# MD015A_MCU_USB2HUB.net
KiCad netlist of a schematic drawn in Altium Designer
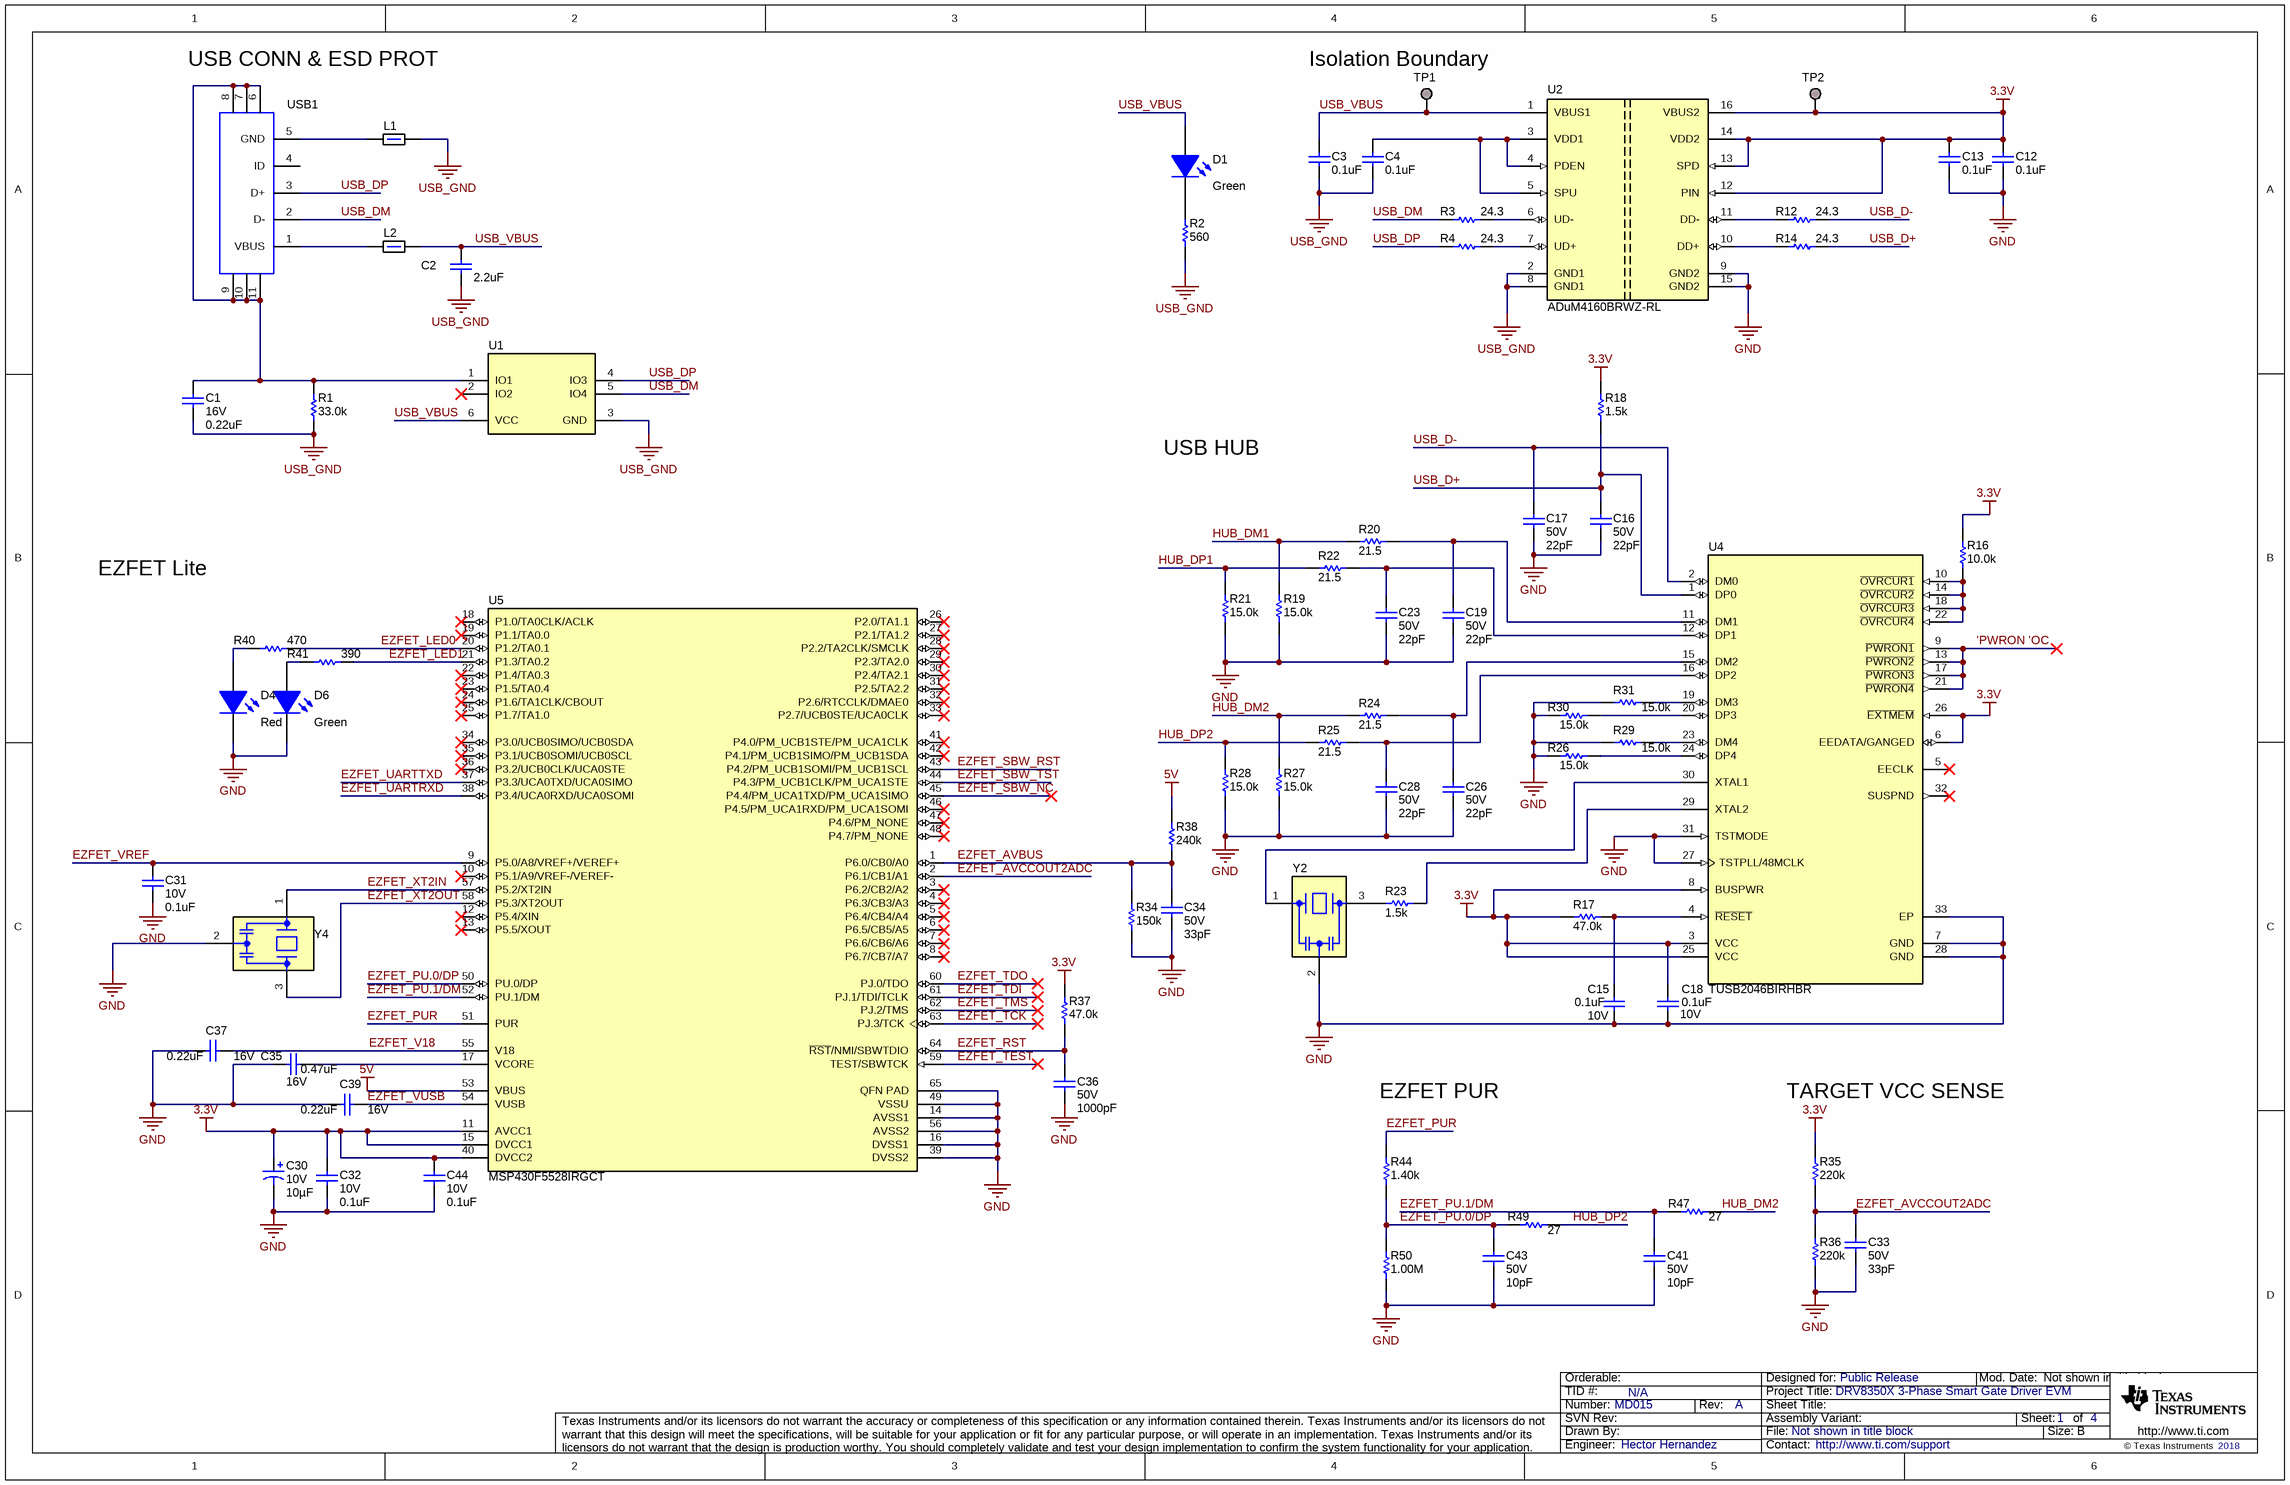
[diagram p0: MD015A_MCU_USB2HUB.SchDoc]

(export (version "E")
  (design (tool "Eeschema 10.0.6"))
  (components
    (comp (ref "C1")
      (value "GRM155R71C224KA12D")
      (footprint "0402L")
      (description "CAP, CERM, 0.22 uF, 16 V, +/- 10%, X7R, 0402")
      (fields
        (field (name "MANUFACTURER") "MuRata")
        (field (name "VDC_V") "16V")
        (field (name "VALUEDISPLAYED") "0.22uF")
      )
      (libsource (lib "Altium Vault - TI") (part "Capacitor"))
    )
    (comp (ref "C2")
      (value "GRM155R60J225KE95D")
      (footprint "0402L")
      (description "CAP, CERM, 2.2 uF, 6.3 V, +/- 10%, X5R, 0402")
      (fields (field (name "VALUEDISPLAYED") "2.2uF") (field (name "MANUFACTURER") "MuRata"))
      (libsource (lib "Altium Vault - TI") (part "Capacitor"))
    )
    (comp (ref "C3")
      (value "GRM155R71A104KA01D")
      (footprint "0402L")
      (description "CAP, CERM, 0.1 uF, 10 V, +/- 10%, X7R, 0402")
      (fields (field (name "VALUEDISPLAYED") "0.1uF") (field (name "MANUFACTURER") "MuRata"))
      (libsource (lib "Altium Vault - TI") (part "Capacitor"))
    )
    (comp (ref "C4")
      (value "GRM155R71A104KA01D")
      (footprint "0402L")
      (description "CAP, CERM, 0.1 uF, 10 V, +/- 10%, X7R, 0402")
      (fields (field (name "VALUEDISPLAYED") "0.1uF") (field (name "MANUFACTURER") "MuRata"))
      (libsource (lib "Altium Vault - TI") (part "Capacitor"))
    )
    (comp (ref "C12")
      (value "GRM155R71A104KA01D")
      (footprint "0402L")
      (description "CAP, CERM, 0.1 uF, 10 V, +/- 10%, X7R, 0402")
      (fields (field (name "VALUEDISPLAYED") "0.1uF") (field (name "MANUFACTURER") "MuRata"))
      (libsource (lib "Altium Vault - TI") (part "Capacitor"))
    )
    (comp (ref "C13")
      (value "GRM155R71A104KA01D")
      (footprint "0402L")
      (description "CAP, CERM, 0.1 uF, 10 V, +/- 10%, X7R, 0402")
      (fields (field (name "VALUEDISPLAYED") "0.1uF") (field (name "MANUFACTURER") "MuRata"))
      (libsource (lib "Altium Vault - TI") (part "Capacitor"))
    )
    (comp (ref "C15")
      (value "885012105010")
      (footprint "0402L")
      (description "CAP, CERM, 0.1 uF, 10 V, +/- 20%, X5R, 0402")
      (fields
        (field (name "MANUFACTURER") "Wurth Elektronik")
        (field (name "VDC_V") "10V")
        (field (name "VALUEDISPLAYED") "0.1uF")
      )
      (libsource (lib "Altium Vault - TI") (part "Capacitor"))
    )
    (comp (ref "C16")
      (value "C1005C0G1H220J050BA")
      (footprint "0402L")
      (description "CAP, CERM, 22 pF, 50 V, +/- 5%, C0G/NP0, 0402")
      (fields
        (field (name "MANUFACTURER") "TDK")
        (field (name "VDC_V") "50V")
        (field (name "VALUEDISPLAYED") "22pF")
      )
      (libsource (lib "Altium Vault - TI") (part "Capacitor"))
    )
    (comp (ref "C17")
      (value "C1005C0G1H220J050BA")
      (footprint "0402L")
      (description "CAP, CERM, 22 pF, 50 V, +/- 5%, C0G/NP0, 0402")
      (fields
        (field (name "MANUFACTURER") "TDK")
        (field (name "VDC_V") "50V")
        (field (name "VALUEDISPLAYED") "22pF")
      )
      (libsource (lib "Altium Vault - TI") (part "Capacitor"))
    )
    (comp (ref "C18")
      (value "885012105010")
      (footprint "0402L")
      (description "CAP, CERM, 0.1 uF, 10 V, +/- 20%, X5R, 0402")
      (fields
        (field (name "MANUFACTURER") "Wurth Elektronik")
        (field (name "VDC_V") "10V")
        (field (name "VALUEDISPLAYED") "0.1uF")
      )
      (libsource (lib "Altium Vault - TI") (part "Capacitor"))
    )
    (comp (ref "C19")
      (value "C1005C0G1H220J050BA")
      (footprint "0402L")
      (description "CAP, CERM, 22 pF, 50 V, +/- 5%, C0G/NP0, 0402")
      (fields
        (field (name "MANUFACTURER") "TDK")
        (field (name "VDC_V") "50V")
        (field (name "VALUEDISPLAYED") "22pF")
      )
      (libsource (lib "Altium Vault - TI") (part "Capacitor"))
    )
    (comp (ref "C23")
      (value "C1005C0G1H220J050BA")
      (footprint "0402L")
      (description "CAP, CERM, 22 pF, 50 V, +/- 5%, C0G/NP0, 0402")
      (fields
        (field (name "MANUFACTURER") "TDK")
        (field (name "VDC_V") "50V")
        (field (name "VALUEDISPLAYED") "22pF")
      )
      (libsource (lib "Altium Vault - TI") (part "Capacitor"))
    )
    (comp (ref "C26")
      (value "C1005C0G1H220J050BA")
      (footprint "0402L")
      (description "CAP, CERM, 22 pF, 50 V, +/- 5%, C0G/NP0, 0402")
      (fields
        (field (name "MANUFACTURER") "TDK")
        (field (name "VDC_V") "50V")
        (field (name "VALUEDISPLAYED") "22pF")
      )
      (libsource (lib "Altium Vault - TI") (part "Capacitor"))
    )
    (comp (ref "C28")
      (value "C1005C0G1H220J050BA")
      (footprint "0402L")
      (description "CAP, CERM, 22 pF, 50 V, +/- 5%, C0G/NP0, 0402")
      (fields
        (field (name "MANUFACTURER") "TDK")
        (field (name "VDC_V") "50V")
        (field (name "VALUEDISPLAYED") "22pF")
      )
      (libsource (lib "Altium Vault - TI") (part "Capacitor"))
    )
    (comp (ref "C30")
      (value "T520A106M010ATE080")
      (footprint "3216-18")
      (description "CAP, Tantalum Polymer, 10 µF, 10 V,+/- 20%, 0.08 ohm, 3216-18 SMD")
      (fields
        (field (name "VDC_V") "10V")
        (field (name "MANUFACTURER") "Kemet")
        (field (name "VALUEDISPLAYED") "10µF")
      )
      (libsource (lib "Altium Vault - TI") (part "Cap_Polarized"))
    )
    (comp (ref "C31")
      (value "885012105010")
      (footprint "0402L")
      (description "CAP, CERM, 0.1 uF, 10 V, +/- 20%, X5R, 0402")
      (fields
        (field (name "MANUFACTURER") "Wurth Elektronik")
        (field (name "VDC_V") "10V")
        (field (name "VALUEDISPLAYED") "0.1uF")
      )
      (libsource (lib "Altium Vault - TI") (part "Capacitor"))
    )
    (comp (ref "C32")
      (value "885012105010")
      (footprint "0402L")
      (description "CAP, CERM, 0.1 uF, 10 V, +/- 20%, X5R, 0402")
      (fields
        (field (name "MANUFACTURER") "Wurth Elektronik")
        (field (name "VDC_V") "10V")
        (field (name "VALUEDISPLAYED") "0.1uF")
      )
      (libsource (lib "Altium Vault - TI") (part "Capacitor"))
    )
    (comp (ref "C33")
      (value "C0603C330J5GACTU")
      (footprint "0603L")
      (description "CAP, CERM, 33 pF, 50 V, +/- 5%, C0G/NP0, 0603")
      (fields
        (field (name "MANUFACTURER") "Kemet")
        (field (name "VDC_V") "50V")
        (field (name "VALUEDISPLAYED") "33pF")
      )
      (libsource (lib "Altium Vault - TI") (part "Capacitor"))
    )
    (comp (ref "C34")
      (value "C0603C330J5GACTU")
      (footprint "0603L")
      (description "CAP, CERM, 33 pF, 50 V, +/- 5%, C0G/NP0, 0603")
      (fields
        (field (name "MANUFACTURER") "Kemet")
        (field (name "VDC_V") "50V")
        (field (name "VALUEDISPLAYED") "33pF")
      )
      (libsource (lib "Altium Vault - TI") (part "Capacitor"))
    )
    (comp (ref "C35")
      (value "GCM188R71C474KA55D")
      (footprint "0603L")
      (description "CAP, CERM, 0.47 uF, 16 V, +/- 10%, X7R, AEC-Q200 Grade 1, 0603")
      (fields
        (field (name "MANUFACTURER") "MuRata")
        (field (name "VDC_V") "16V")
        (field (name "VALUEDISPLAYED") "0.47uF")
      )
      (libsource (lib "Altium Vault - TI") (part "Capacitor"))
    )
    (comp (ref "C36")
      (value "885012205061")
      (footprint "0402L")
      (description "CAP, CERM, 1000 pF, 50 V, +/- 10%, X7R, 0402")
      (fields
        (field (name "MANUFACTURER") "Wurth Elektronik")
        (field (name "VDC_V") "50V")
        (field (name "VALUEDISPLAYED") "1000pF")
      )
      (libsource (lib "Altium Vault - TI") (part "Capacitor"))
    )
    (comp (ref "C37")
      (value "C1005X5R1C224K050BB")
      (footprint "0402L")
      (description "CAP, CERM, 0.22 uF, 16 V, +/- 10%, X5R, 0402")
      (fields
        (field (name "MANUFACTURER") "TDK")
        (field (name "VDC_V") "16V")
        (field (name "VALUEDISPLAYED") "0.22uF")
      )
      (libsource (lib "Altium Vault - TI") (part "Capacitor"))
    )
    (comp (ref "C39")
      (value "C1005X5R1C224K050BB")
      (footprint "0402L")
      (description "CAP, CERM, 0.22 uF, 16 V, +/- 10%, X5R, 0402")
      (fields
        (field (name "MANUFACTURER") "TDK")
        (field (name "VDC_V") "16V")
        (field (name "VALUEDISPLAYED") "0.22uF")
      )
      (libsource (lib "Altium Vault - TI") (part "Capacitor"))
    )
    (comp (ref "C41")
      (value "04025U100CAT2A")
      (footprint "0402L")
      (description "CAP, CERM, 10 pF, 50 V,+/- 2.5%, C0G/NP0, AEC-Q200 Grade 1, 0402")
      (fields
        (field (name "MANUFACTURER") "AVX")
        (field (name "VDC_V") "50V")
        (field (name "VALUEDISPLAYED") "10pF")
      )
      (libsource (lib "Altium Vault - TI") (part "Capacitor"))
    )
    (comp (ref "C43")
      (value "04025U100CAT2A")
      (footprint "0402L")
      (description "CAP, CERM, 10 pF, 50 V,+/- 2.5%, C0G/NP0, AEC-Q200 Grade 1, 0402")
      (fields
        (field (name "MANUFACTURER") "AVX")
        (field (name "VDC_V") "50V")
        (field (name "VALUEDISPLAYED") "10pF")
      )
      (libsource (lib "Altium Vault - TI") (part "Capacitor"))
    )
    (comp (ref "C44")
      (value "885012105010")
      (footprint "0402L")
      (description "CAP, CERM, 0.1 uF, 10 V, +/- 20%, X5R, 0402")
      (fields
        (field (name "MANUFACTURER") "Wurth Elektronik")
        (field (name "VDC_V") "10V")
        (field (name "VALUEDISPLAYED") "0.1uF")
      )
      (libsource (lib "Altium Vault - TI") (part "Capacitor"))
    )
    (comp (ref "D1")
      (value "Green")
      (footprint "LTST-C170KGKT_Green")
      (description "LED, Green, SMD")
      (fields (field (name "MANUFACTURER") "Lite-On") (field (name "PARTNUMBER") "LTST-C170KGKT"))
      (libsource (lib "Altium Vault - TI") (part "LED"))
    )
    (comp (ref "D4")
      (value "Red")
      (footprint "LED_LTST-C190_Red")
      (description "LED, Red, SMD")
      (fields (field (name "MANUFACTURER") "Lite-On") (field (name "PARTNUMBER") "LTST-C190CKT"))
      (libsource (lib "Altium Vault - TI") (part "LED"))
    )
    (comp (ref "D6")
      (value "Green")
      (footprint "LED_LTST-C190")
      (description "LED, Green, SMD")
      (fields (field (name "MANUFACTURER") "Lite-On") (field (name "PARTNUMBER") "LTST-C190GKT"))
      (libsource (lib "Altium Vault - TI") (part "LED"))
    )
    (comp (ref "L1")
      (value "742792620")
      (footprint "0603L")
      (description "Ferrite Bead, 100 ohm @ 100 MHz, 0.5 A, 0603")
      (fields (field (name "MANUFACTURER") "Wurth Elektronik"))
      (libsource (lib "Altium Vault - TI") (part "Ferrite_Bead"))
    )
    (comp (ref "L2")
      (value "742792620")
      (footprint "0603L")
      (description "Ferrite Bead, 100 ohm @ 100 MHz, 0.5 A, 0603")
      (fields (field (name "MANUFACTURER") "Wurth Elektronik"))
      (libsource (lib "Altium Vault - TI") (part "Ferrite_Bead"))
    )
    (comp (ref "R1")
      (value "RC0402FR-0733KL")
      (footprint "0402L")
      (description "RES, 33.0 k, 1%, 0.063 W, 0402")
      (fields (field (name "MANUFACTURER") "Yageo America") (field (name "VALUEDISPLAYED") "33.0k"))
      (libsource (lib "Altium Vault - TI") (part "Resistor"))
    )
    (comp (ref "R2")
      (value "RG1608P-561-B-T5")
      (footprint "0603L")
      (description "RES, 560, 0.1%, 0.1 W, 0603")
      (fields (field (name "MANUFACTURER") "Susumu Co Ltd") (field (name "VALUEDISPLAYED") "560"))
      (libsource (lib "Altium Vault - TI") (part "Resistor"))
    )
    (comp (ref "R3")
      (value "CRCW040224R3FKED")
      (footprint "0402L")
      (description "RES, 24.3, 1%, 0.063 W, AEC-Q200 Grade 0, 0402")
      (fields (field (name "VALUEDISPLAYED") "24.3") (field (name "MANUFACTURER") "Vishay-Dale"))
      (libsource (lib "Altium Vault - TI") (part "Resistor"))
    )
    (comp (ref "R4")
      (value "CRCW040224R3FKED")
      (footprint "0402L")
      (description "RES, 24.3, 1%, 0.063 W, AEC-Q200 Grade 0, 0402")
      (fields (field (name "VALUEDISPLAYED") "24.3") (field (name "MANUFACTURER") "Vishay-Dale"))
      (libsource (lib "Altium Vault - TI") (part "Resistor"))
    )
    (comp (ref "R12")
      (value "CRCW040224R3FKED")
      (footprint "0402L")
      (description "RES, 24.3, 1%, 0.063 W, AEC-Q200 Grade 0, 0402")
      (fields (field (name "VALUEDISPLAYED") "24.3") (field (name "MANUFACTURER") "Vishay-Dale"))
      (libsource (lib "Altium Vault - TI") (part "Resistor"))
    )
    (comp (ref "R14")
      (value "CRCW040224R3FKED")
      (footprint "0402L")
      (description "RES, 24.3, 1%, 0.063 W, AEC-Q200 Grade 0, 0402")
      (fields (field (name "VALUEDISPLAYED") "24.3") (field (name "MANUFACTURER") "Vishay-Dale"))
      (libsource (lib "Altium Vault - TI") (part "Resistor"))
    )
    (comp (ref "R16")
      (value "MCR01MRTF1002")
      (footprint "0402L")
      (description "RES, 10.0 k, 0.1%, 0.063 W, 0402")
      (fields (field (name "MANUFACTURER") "Rohm") (field (name "VALUEDISPLAYED") "10.0k"))
      (libsource (lib "Altium Vault - TI") (part "Resistor"))
    )
    (comp (ref "R17")
      (value "RC0402FR-0747KL")
      (footprint "0402L")
      (description "RES, 47.0 k, 1%, 0.0625 W, 0402")
      (fields (field (name "MANUFACTURER") "Yageo America") (field (name "VALUEDISPLAYED") "47.0k"))
      (libsource (lib "Altium Vault - TI") (part "Resistor"))
    )
    (comp (ref "R18")
      (value "CRCW04021K50JNED")
      (footprint "0402L")
      (description "RES, 1.5 k, 5%, 0.063 W, AEC-Q200 Grade 0, 0402")
      (fields (field (name "MANUFACTURER") "Vishay-Dale") (field (name "VALUEDISPLAYED") "1.5k"))
      (libsource (lib "Altium Vault - TI") (part "Resistor"))
    )
    (comp (ref "R19")
      (value "RC0402FR-0715KL")
      (footprint "0402L")
      (description "RES, 15.0 k, 1%, 0.063 W, 0402")
      (fields (field (name "MANUFACTURER") "Yageo America") (field (name "VALUEDISPLAYED") "15.0k"))
      (libsource (lib "Altium Vault - TI") (part "Resistor"))
    )
    (comp (ref "R20")
      (value "CRCW040221R5FKED")
      (footprint "0402L")
      (description "RES, 21.5, 1%, 0.063 W, AEC-Q200 Grade 0, 0402")
      (fields (field (name "MANUFACTURER") "Vishay-Dale") (field (name "VALUEDISPLAYED") "21.5"))
      (libsource (lib "Altium Vault - TI") (part "Resistor"))
    )
    (comp (ref "R21")
      (value "RC0402FR-0715KL")
      (footprint "0402L")
      (description "RES, 15.0 k, 1%, 0.063 W, 0402")
      (fields (field (name "MANUFACTURER") "Yageo America") (field (name "VALUEDISPLAYED") "15.0k"))
      (libsource (lib "Altium Vault - TI") (part "Resistor"))
    )
    (comp (ref "R22")
      (value "CRCW040221R5FKED")
      (footprint "0402L")
      (description "RES, 21.5, 1%, 0.063 W, AEC-Q200 Grade 0, 0402")
      (fields (field (name "MANUFACTURER") "Vishay-Dale") (field (name "VALUEDISPLAYED") "21.5"))
      (libsource (lib "Altium Vault - TI") (part "Resistor"))
    )
    (comp (ref "R23")
      (value "CRCW04021K50JNED")
      (footprint "0402L")
      (description "RES, 1.5 k, 5%, 0.063 W, AEC-Q200 Grade 0, 0402")
      (fields (field (name "MANUFACTURER") "Vishay-Dale") (field (name "VALUEDISPLAYED") "1.5k"))
      (libsource (lib "Altium Vault - TI") (part "Resistor"))
    )
    (comp (ref "R24")
      (value "CRCW040221R5FKED")
      (footprint "0402L")
      (description "RES, 21.5, 1%, 0.063 W, AEC-Q200 Grade 0, 0402")
      (fields (field (name "MANUFACTURER") "Vishay-Dale") (field (name "VALUEDISPLAYED") "21.5"))
      (libsource (lib "Altium Vault - TI") (part "Resistor"))
    )
    (comp (ref "R25")
      (value "CRCW040221R5FKED")
      (footprint "0402L")
      (description "RES, 21.5, 1%, 0.063 W, AEC-Q200 Grade 0, 0402")
      (fields (field (name "MANUFACTURER") "Vishay-Dale") (field (name "VALUEDISPLAYED") "21.5"))
      (libsource (lib "Altium Vault - TI") (part "Resistor"))
    )
    (comp (ref "R26")
      (value "RC0402FR-0715KL")
      (footprint "0402L")
      (description "RES, 15.0 k, 1%, 0.063 W, 0402")
      (fields (field (name "MANUFACTURER") "Yageo America") (field (name "VALUEDISPLAYED") "15.0k"))
      (libsource (lib "Altium Vault - TI") (part "Resistor"))
    )
    (comp (ref "R27")
      (value "RC0402FR-0715KL")
      (footprint "0402L")
      (description "RES, 15.0 k, 1%, 0.063 W, 0402")
      (fields (field (name "MANUFACTURER") "Yageo America") (field (name "VALUEDISPLAYED") "15.0k"))
      (libsource (lib "Altium Vault - TI") (part "Resistor"))
    )
    (comp (ref "R28")
      (value "RC0402FR-0715KL")
      (footprint "0402L")
      (description "RES, 15.0 k, 1%, 0.063 W, 0402")
      (fields (field (name "MANUFACTURER") "Yageo America") (field (name "VALUEDISPLAYED") "15.0k"))
      (libsource (lib "Altium Vault - TI") (part "Resistor"))
    )
    (comp (ref "R29")
      (value "RC0402FR-0715KL")
      (footprint "0402L")
      (description "RES, 15.0 k, 1%, 0.063 W, 0402")
      (fields (field (name "MANUFACTURER") "Yageo America") (field (name "VALUEDISPLAYED") "15.0k"))
      (libsource (lib "Altium Vault - TI") (part "Resistor"))
    )
    (comp (ref "R30")
      (value "RC0402FR-0715KL")
      (footprint "0402L")
      (description "RES, 15.0 k, 1%, 0.063 W, 0402")
      (fields (field (name "MANUFACTURER") "Yageo America") (field (name "VALUEDISPLAYED") "15.0k"))
      (libsource (lib "Altium Vault - TI") (part "Resistor"))
    )
    (comp (ref "R31")
      (value "RC0402FR-0715KL")
      (footprint "0402L")
      (description "RES, 15.0 k, 1%, 0.063 W, 0402")
      (fields (field (name "MANUFACTURER") "Yageo America") (field (name "VALUEDISPLAYED") "15.0k"))
      (libsource (lib "Altium Vault - TI") (part "Resistor"))
    )
    (comp (ref "R34")
      (value "ERJ-2RKF1503X")
      (footprint "0402L")
      (description "RES, 150 k, 1%, 0.1 W, AEC-Q200 Grade 0, 0402")
      (fields (field (name "MANUFACTURER") "Panasonic") (field (name "VALUEDISPLAYED") "150k"))
      (libsource (lib "Altium Vault - TI") (part "Resistor"))
    )
    (comp (ref "R35")
      (value "RC0402FR-07220KL")
      (footprint "0402L")
      (description "RES, 220 k, 1%, 0.0625 W, 0402")
      (fields (field (name "MANUFACTURER") "Yageo America") (field (name "VALUEDISPLAYED") "220k"))
      (libsource (lib "Altium Vault - TI") (part "Resistor"))
    )
    (comp (ref "R36")
      (value "RC0402FR-07220KL")
      (footprint "0402L")
      (description "RES, 220 k, 1%, 0.0625 W, 0402")
      (fields (field (name "MANUFACTURER") "Yageo America") (field (name "VALUEDISPLAYED") "220k"))
      (libsource (lib "Altium Vault - TI") (part "Resistor"))
    )
    (comp (ref "R37")
      (value "RC0402FR-0747KL")
      (footprint "0402L")
      (description "RES, 47.0 k, 1%, 0.0625 W, 0402")
      (fields (field (name "MANUFACTURER") "Yageo America") (field (name "VALUEDISPLAYED") "47.0k"))
      (libsource (lib "Altium Vault - TI") (part "Resistor"))
    )
    (comp (ref "R38")
      (value "ERJ-2RKF2403X")
      (footprint "0402L")
      (description "RES, 240 k, 1%, 0.1 W, AEC-Q200 Grade 0, 0402")
      (fields (field (name "MANUFACTURER") "Panasonic") (field (name "VALUEDISPLAYED") "240k"))
      (libsource (lib "Altium Vault - TI") (part "Resistor"))
    )
    (comp (ref "R40")
      (value "ERJ-2RKF4700X")
      (footprint "0402L")
      (description "RES, 470, 1%, 0.1 W, AEC-Q200 Grade 0, 0402")
      (fields (field (name "MANUFACTURER") "Panasonic") (field (name "VALUEDISPLAYED") "470"))
      (libsource (lib "Altium Vault - TI") (part "Resistor"))
    )
    (comp (ref "R41")
      (value "CRCW0402390RJNED")
      (footprint "0402L")
      (description "RES, 390, 5%, 0.063 W, AEC-Q200 Grade 0, 0402")
      (fields (field (name "MANUFACTURER") "Vishay-Dale") (field (name "VALUEDISPLAYED") "390"))
      (libsource (lib "Altium Vault - TI") (part "Resistor"))
    )
    (comp (ref "R44")
      (value "ERJ-2RKF1401X")
      (footprint "0402L")
      (description "RES, 1.40 k, 1%, 0.1 W, 0402")
      (fields (field (name "MANUFACTURER") "Panasonic") (field (name "VALUEDISPLAYED") "1.40k"))
      (libsource (lib "Altium Vault - TI") (part "Resistor"))
    )
    (comp (ref "R47")
      (value "CRCW040227R0JNED")
      (footprint "0402L")
      (description "RES, 27, 5%, 0.063 W, AEC-Q200 Grade 0, 0402")
      (fields (field (name "MANUFACTURER") "Vishay-Dale") (field (name "VALUEDISPLAYED") "27"))
      (libsource (lib "Altium Vault - TI") (part "Resistor"))
    )
    (comp (ref "R49")
      (value "CRCW040227R0JNED")
      (footprint "0402L")
      (description "RES, 27, 5%, 0.063 W, AEC-Q200 Grade 0, 0402")
      (fields (field (name "MANUFACTURER") "Vishay-Dale") (field (name "VALUEDISPLAYED") "27"))
      (libsource (lib "Altium Vault - TI") (part "Resistor"))
    )
    (comp (ref "R50")
      (value "ERJ-2RKF1004X")
      (footprint "0402L")
      (description "RES, 1.00 M, 1%, 0.1 W, 0402")
      (fields (field (name "MANUFACTURER") "Panasonic") (field (name "VALUEDISPLAYED") "1.00M"))
      (libsource (lib "Altium Vault - TI") (part "Resistor"))
    )
    (comp (ref "TP1")
      (value "TP_SM_1MM")
      (footprint "TP_SM_1MM")
      (description "1mm Test Point, SMT")
      (fields (field (name "MANUFACTURER") "Any"))
      (libsource (lib "Altium Vault - TI") (part "TESTPOINT"))
    )
    (comp (ref "TP2")
      (value "TP_SM_1MM")
      (footprint "TP_SM_1MM")
      (description "1mm Test Point, SMT")
      (fields (field (name "MANUFACTURER") "Any"))
      (libsource (lib "Altium Vault - TI") (part "TESTPOINT"))
    )
    (comp (ref "U1")
      (value "TPD4E004DRYR")
      (footprint "DRY0006A")
      (description "4-Channel ESD Protection Array for High-Speed Data Interfaces, DRY0006A (USON-6)")
      (fields (field (name "MANUFACTURER") "Texas Instruments"))
      (libsource (lib "Altium Vault - TI") (part "TI-TPD4E004-SON_DRY-6"))
    )
    (comp (ref "U2")
      (value "ADuM4160BRWZ-RL")
      (footprint "SOIC-16")
      (description "Full/Low Speed 5 kV USB Digital Isolator, SOIC-16")
      (fields (field (name "MANUFACTURER") "Analog Devices"))
      (libsource (lib "Altium Vault - TI") (part "ADUM4160"))
    )
    (comp (ref "U4")
      (value "TUSB2046BIRHBR")
      (footprint "RHB0032E")
      (description "4-Port Full-Speed USB Hub, 3.3V, -40 to 85 degC, 32-Pin QFN (RHB), Green (RoHS & no Sb/Br)")
      (fields (field (name "PARTNUMBER") "TUSB2046BIRHBR") (field (name "MANUFACTURER") "Texas Instruments"))
      (libsource (lib "Altium Vault - TI") (part "TI-TUSB2046B-QFN_RHB-32"))
    )
    (comp (ref "U5")
      (value "MSP430F5528IRGCT")
      (footprint "RGC0064B")
      (fields
        (field (name "PARTNUMBER") "MSP430F5528IRGCT")
        (field (name "MANUFACTURER") "Texas Instruments")
        (field (name "ALTERNATE PARTNUMBER") "MSP430F5528IRGCR")
      )
      (libsource (lib "Altium Vault - TI") (part "MSP430F5528IRGC"))
    )
    (comp (ref "USB1")
      (value "1051640001")
      (footprint "Molex_1051640001")
      (description "Receptacle, USB 2.0, Micro B, 5 Position, R/A, SMT")
      (fields (field (name "MANUFACTURER") "Molex"))
      (libsource (lib "Altium Vault - TI") (part "CONN_USB_MicroMini_6Shld"))
    )
    (comp (ref "Y2")
      (value "CSTNR6M00GH5L000R0")
      (footprint "MuRata_CSTNR")
      (description "Oscillator, 6 MHz, 700 ppm, 39 pF, SMD")
      (fields (field (name "MANUFACTURER") "MuRata"))
      (libsource (lib "") (part "OSC_CSTCE_1"))
    )
    (comp (ref "Y4")
      (value "CSTNR4M00GH5L000R0")
      (footprint "MuRata_CSTNR")
      (description "Oscillator, 4 MHz, 700 ppm, 39 pF, SMD")
      (fields (field (name "MANUFACTURER") "MuRata"))
      (libsource (lib "Altium Vault - TI") (part "OSC_CSTCE"))
    )
  )
  (nets
    (net (code "1") (name "/'PWRON 'OC") (class "Default")
      (node (ref "U4") (pin "13") (pinfunction "~{PWRON2}_13") (pintype "output"))
      (node (ref "U4") (pin "17") (pinfunction "~{PWRON3}_17") (pintype "output"))
      (node (ref "U4") (pin "21") (pinfunction "~{PWRON4}_21") (pintype "output"))
      (node (ref "U4") (pin "9") (pinfunction "~{PWRON1}_9") (pintype "output"))
    )
    (net (code "2") (name "/EZFET_AVBUS") (class "Default")
      (node (ref "C34") (pin "1") (pinfunction "1_1") (pintype "passive"))
      (node (ref "R34") (pin "2") (pinfunction "2_2") (pintype "passive"))
      (node (ref "R38") (pin "2") (pinfunction "2_2") (pintype "passive"))
      (node (ref "U5") (pin "1") (pinfunction "P6.0/CB0/A0_1") (pintype "bidirectional"))
    )
    (net (code "3") (name "/EZFET_AVCCOUT2ADC") (class "Default")
      (node (ref "C33") (pin "1") (pinfunction "1_1") (pintype "passive"))
      (node (ref "R35") (pin "1") (pinfunction "1_1") (pintype "passive"))
      (node (ref "R36") (pin "2") (pinfunction "2_2") (pintype "passive"))
      (node (ref "U5") (pin "2") (pinfunction "P6.1/CB1/A1_2") (pintype "bidirectional"))
    )
    (net (code "4") (name "/EZFET_LED0") (class "Default")
      (node (ref "R40") (pin "2") (pinfunction "2_2") (pintype "passive"))
      (node (ref "U5") (pin "20") (pinfunction "P1.2/TA0.1_20") (pintype "bidirectional"))
    )
    (net (code "5") (name "/EZFET_LED1") (class "Default")
      (node (ref "R41") (pin "1") (pinfunction "1_1") (pintype "passive"))
      (node (ref "U5") (pin "21") (pinfunction "P1.3/TA0.2_21") (pintype "bidirectional"))
    )
    (net (code "6") (name "/EZFET_PU.0{slash}DP") (class "Default")
      (node (ref "C43") (pin "1") (pinfunction "1_1") (pintype "passive"))
      (node (ref "R44") (pin "1") (pinfunction "1_1") (pintype "passive"))
      (node (ref "R49") (pin "2") (pinfunction "2_2") (pintype "passive"))
      (node (ref "R50") (pin "2") (pinfunction "2_2") (pintype "passive"))
      (node (ref "U5") (pin "50") (pinfunction "PU.0/DP_50") (pintype "bidirectional"))
    )
    (net (code "7") (name "/EZFET_PU.1{slash}DM") (class "Default")
      (node (ref "C41") (pin "1") (pinfunction "1_1") (pintype "passive"))
      (node (ref "R47") (pin "2") (pinfunction "2_2") (pintype "passive"))
      (node (ref "U5") (pin "52") (pinfunction "PU.1/DM_52") (pintype "bidirectional"))
    )
    (net (code "8") (name "/EZFET_PUR") (class "Default")
      (node (ref "R44") (pin "2") (pinfunction "2_2") (pintype "passive"))
      (node (ref "U5") (pin "51") (pinfunction "PUR_51") (pintype "passive"))
    )
    (net (code "9") (name "/EZFET_RST") (class "Default")
      (node (ref "C36") (pin "1") (pinfunction "1_1") (pintype "passive"))
      (node (ref "R37") (pin "1") (pinfunction "1_1") (pintype "passive"))
      (node (ref "U5") (pin "64") (pinfunction "~{RST}/NMI/SBWTDIO_64") (pintype "bidirectional"))
    )
    (net (code "10") (name "/EZFET_SBW_NC") (class "Default")
      (node (ref "U5") (pin "45") (pinfunction "P4.4/PM_UCA1TXD/PM_UCA1SIMO_45") (pintype "bidirectional+no_connect"))
    )
    (net (code "11") (name "/EZFET_SBW_RST") (class "Default")
      (node (ref "U5") (pin "43") (pinfunction "P4.2/PM_UCB1SOMI/PM_UCB1SCL_43") (pintype "bidirectional"))
    )
    (net (code "12") (name "/EZFET_SBW_TST") (class "Default")
      (node (ref "U5") (pin "44") (pinfunction "P4.3/PM_UCB1CLK/PM_UCA1STE_44") (pintype "bidirectional"))
    )
    (net (code "13") (name "/EZFET_TCK") (class "Default")
      (node (ref "U5") (pin "63") (pinfunction "PJ.3/TCK_63") (pintype "bidirectional+no_connect"))
    )
    (net (code "14") (name "/EZFET_TDI") (class "Default")
      (node (ref "U5") (pin "61") (pinfunction "PJ.1/TDI/TCLK_61") (pintype "bidirectional+no_connect"))
    )
    (net (code "15") (name "/EZFET_TDO") (class "Default")
      (node (ref "U5") (pin "60") (pinfunction "PJ.0/TDO_60") (pintype "bidirectional+no_connect"))
    )
    (net (code "16") (name "/EZFET_TEST") (class "Default")
      (node (ref "U5") (pin "59") (pinfunction "TEST/SBWTCK_59") (pintype "input+no_connect"))
    )
    (net (code "17") (name "/EZFET_TMS") (class "Default")
      (node (ref "U5") (pin "62") (pinfunction "PJ.2/TMS_62") (pintype "bidirectional+no_connect"))
    )
    (net (code "18") (name "/EZFET_UARTRXD") (class "Default")
      (node (ref "U5") (pin "38") (pinfunction "P3.4/UCA0RXD/UCA0SOMI_38") (pintype "bidirectional"))
    )
    (net (code "19") (name "/EZFET_UARTTXD") (class "Default")
      (node (ref "U5") (pin "37") (pinfunction "P3.3/UCA0TXD/UCA0SIMO_37") (pintype "bidirectional"))
    )
    (net (code "20") (name "/EZFET_V18") (class "Default")
      (node (ref "C37") (pin "2") (pinfunction "2_2") (pintype "passive"))
      (node (ref "U5") (pin "55") (pinfunction "V18_55") (pintype "passive"))
    )
    (net (code "21") (name "/EZFET_VREF") (class "Default")
      (node (ref "C31") (pin "1") (pinfunction "1_1") (pintype "passive"))
      (node (ref "U5") (pin "9") (pinfunction "P5.0/A8/VREF+/VEREF+_9") (pintype "bidirectional"))
    )
    (net (code "22") (name "/EZFET_VUSB") (class "Default")
      (node (ref "C39") (pin "2") (pinfunction "2_2") (pintype "passive"))
      (node (ref "U5") (pin "54") (pinfunction "VUSB_54") (pintype "power_in"))
    )
    (net (code "23") (name "/EZFET_XT2IN") (class "Default")
      (node (ref "U5") (pin "57") (pinfunction "P5.2/XT2IN_57") (pintype "bidirectional"))
      (node (ref "Y4") (pin "1") (pinfunction "In_1") (pintype "passive"))
    )
    (net (code "24") (name "/EZFET_XT2OUT") (class "Default")
      (node (ref "U5") (pin "58") (pinfunction "P5.3/XT2OUT_58") (pintype "bidirectional"))
      (node (ref "Y4") (pin "3") (pinfunction "Out_3") (pintype "passive"))
    )
    (net (code "25") (name "/HUB_DM1") (class "Default")
      (node (ref "R19") (pin "2") (pinfunction "2_2") (pintype "passive"))
      (node (ref "R20") (pin "2") (pinfunction "2_2") (pintype "passive"))
    )
    (net (code "26") (name "/HUB_DM2") (class "Default")
      (node (ref "R24") (pin "2") (pinfunction "2_2") (pintype "passive"))
      (node (ref "R27") (pin "2") (pinfunction "2_2") (pintype "passive"))
      (node (ref "R47") (pin "1") (pinfunction "1_1") (pintype "passive"))
    )
    (net (code "27") (name "/HUB_DP1") (class "Default")
      (node (ref "R21") (pin "2") (pinfunction "2_2") (pintype "passive"))
      (node (ref "R22") (pin "2") (pinfunction "2_2") (pintype "passive"))
    )
    (net (code "28") (name "/HUB_DP2") (class "Default")
      (node (ref "R25") (pin "2") (pinfunction "2_2") (pintype "passive"))
      (node (ref "R28") (pin "2") (pinfunction "2_2") (pintype "passive"))
      (node (ref "R49") (pin "1") (pinfunction "1_1") (pintype "passive"))
    )
    (net (code "29") (name "/USB_D+") (class "Default")
      (node (ref "C16") (pin "1") (pinfunction "1_1") (pintype "passive"))
      (node (ref "R14") (pin "2") (pinfunction "2_2") (pintype "passive"))
      (node (ref "R18") (pin "1") (pinfunction "1_1") (pintype "passive"))
      (node (ref "U4") (pin "1") (pinfunction "DP0_1") (pintype "bidirectional"))
    )
    (net (code "30") (name "/USB_D-") (class "Default")
      (node (ref "C17") (pin "1") (pinfunction "1_1") (pintype "passive"))
      (node (ref "R12") (pin "2") (pinfunction "2_2") (pintype "passive"))
      (node (ref "U4") (pin "2") (pinfunction "DM0_2") (pintype "bidirectional"))
    )
    (net (code "31") (name "/USB_DM") (class "Default")
      (node (ref "R3") (pin "1") (pinfunction "1_1") (pintype "passive"))
      (node (ref "U1") (pin "5") (pinfunction "IO4_5") (pintype "passive"))
      (node (ref "USB1") (pin "2") (pinfunction "D-_2") (pintype "passive"))
    )
    (net (code "32") (name "/USB_DP") (class "Default")
      (node (ref "R4") (pin "1") (pinfunction "1_1") (pintype "passive"))
      (node (ref "U1") (pin "4") (pinfunction "IO3_4") (pintype "passive"))
      (node (ref "USB1") (pin "3") (pinfunction "D+_3") (pintype "passive"))
    )
    (net (code "33") (name "/USB_VBUS") (class "Default")
      (node (ref "C2") (pin "1") (pinfunction "1_1") (pintype "passive"))
      (node (ref "C3") (pin "2") (pinfunction "2_2") (pintype "passive"))
      (node (ref "D1") (pin "1") (pinfunction "A_1") (pintype "passive"))
      (node (ref "L2") (pin "2") (pinfunction "2_2") (pintype "passive"))
      (node (ref "TP1") (pin "1") (pintype "passive"))
      (node (ref "U1") (pin "6") (pinfunction "VCC_6") (pintype "power_in"))
      (node (ref "U2") (pin "1") (pinfunction "VBUS1_1") (pintype "power_in"))
    )
    (net (code "34") (name "3.3V") (class "Default")
      (node (ref "C12") (pin "2") (pinfunction "2_2") (pintype "passive"))
      (node (ref "C13") (pin "2") (pinfunction "2_2") (pintype "passive"))
      (node (ref "C18") (pin "1") (pinfunction "1_1") (pintype "passive"))
      (node (ref "C30") (pin "1") (pinfunction "+_1") (pintype "passive"))
      (node (ref "C32") (pin "1") (pinfunction "1_1") (pintype "passive"))
      (node (ref "C44") (pin "1") (pinfunction "1_1") (pintype "passive"))
      (node (ref "R16") (pin "2") (pinfunction "2_2") (pintype "passive"))
      (node (ref "R17") (pin "2") (pinfunction "2_2") (pintype "passive"))
      (node (ref "R18") (pin "2") (pinfunction "2_2") (pintype "passive"))
      (node (ref "R35") (pin "2") (pinfunction "2_2") (pintype "passive"))
      (node (ref "R37") (pin "2") (pinfunction "2_2") (pintype "passive"))
      (node (ref "TP2") (pin "1") (pintype "passive"))
      (node (ref "U2") (pin "12") (pinfunction "PIN_12") (pintype "input"))
      (node (ref "U2") (pin "13") (pinfunction "SPD_13") (pintype "input"))
      (node (ref "U2") (pin "14") (pinfunction "VDD2_14") (pintype "power_in"))
      (node (ref "U2") (pin "16") (pinfunction "VBUS2_16") (pintype "power_in"))
      (node (ref "U4") (pin "25") (pinfunction "VCC_25") (pintype "power_in"))
      (node (ref "U4") (pin "26") (pinfunction "~{EXTMEM}_26") (pintype "input"))
      (node (ref "U4") (pin "3") (pinfunction "VCC_3") (pintype "power_in"))
      (node (ref "U4") (pin "6") (pinfunction "EEDATA/GANGED_6") (pintype "bidirectional"))
      (node (ref "U4") (pin "8") (pinfunction "BUSPWR_8") (pintype "input"))
      (node (ref "U5") (pin "11") (pinfunction "AVCC1_11") (pintype "power_in"))
      (node (ref "U5") (pin "15") (pinfunction "DVCC1_15") (pintype "power_in"))
      (node (ref "U5") (pin "40") (pinfunction "DVCC2_40") (pintype "power_in"))
    )
    (net (code "35") (name "5V") (class "Default")
      (node (ref "R38") (pin "1") (pinfunction "1_1") (pintype "passive"))
      (node (ref "U5") (pin "53") (pinfunction "VBUS_53") (pintype "power_in"))
    )
    (net (code "36") (name "GND") (class "Default")
      (node (ref "C12") (pin "1") (pinfunction "1_1") (pintype "passive"))
      (node (ref "C13") (pin "1") (pinfunction "1_1") (pintype "passive"))
      (node (ref "C15") (pin "2") (pinfunction "2_2") (pintype "passive"))
      (node (ref "C16") (pin "2") (pinfunction "2_2") (pintype "passive"))
      (node (ref "C17") (pin "2") (pinfunction "2_2") (pintype "passive"))
      (node (ref "C18") (pin "2") (pinfunction "2_2") (pintype "passive"))
      (node (ref "C19") (pin "2") (pinfunction "2_2") (pintype "passive"))
      (node (ref "C23") (pin "2") (pinfunction "2_2") (pintype "passive"))
      (node (ref "C26") (pin "2") (pinfunction "2_2") (pintype "passive"))
      (node (ref "C28") (pin "2") (pinfunction "2_2") (pintype "passive"))
      (node (ref "C30") (pin "2") (pinfunction "-_2") (pintype "passive"))
      (node (ref "C31") (pin "2") (pinfunction "2_2") (pintype "passive"))
      (node (ref "C32") (pin "2") (pinfunction "2_2") (pintype "passive"))
      (node (ref "C33") (pin "2") (pinfunction "2_2") (pintype "passive"))
      (node (ref "C34") (pin "2") (pinfunction "2_2") (pintype "passive"))
      (node (ref "C35") (pin "1") (pinfunction "1_1") (pintype "passive"))
      (node (ref "C36") (pin "2") (pinfunction "2_2") (pintype "passive"))
      (node (ref "C37") (pin "1") (pinfunction "1_1") (pintype "passive"))
      (node (ref "C39") (pin "1") (pinfunction "1_1") (pintype "passive"))
      (node (ref "C41") (pin "2") (pinfunction "2_2") (pintype "passive"))
      (node (ref "C43") (pin "2") (pinfunction "2_2") (pintype "passive"))
      (node (ref "C44") (pin "2") (pinfunction "2_2") (pintype "passive"))
      (node (ref "D4") (pin "2") (pinfunction "K_2") (pintype "passive"))
      (node (ref "D6") (pin "2") (pinfunction "K_2") (pintype "passive"))
      (node (ref "R19") (pin "1") (pinfunction "1_1") (pintype "passive"))
      (node (ref "R21") (pin "1") (pinfunction "1_1") (pintype "passive"))
      (node (ref "R26") (pin "2") (pinfunction "2_2") (pintype "passive"))
      (node (ref "R27") (pin "1") (pinfunction "1_1") (pintype "passive"))
      (node (ref "R28") (pin "1") (pinfunction "1_1") (pintype "passive"))
      (node (ref "R29") (pin "2") (pinfunction "2_2") (pintype "passive"))
      (node (ref "R30") (pin "2") (pinfunction "2_2") (pintype "passive"))
      (node (ref "R31") (pin "2") (pinfunction "2_2") (pintype "passive"))
      (node (ref "R34") (pin "1") (pinfunction "1_1") (pintype "passive"))
      (node (ref "R36") (pin "1") (pinfunction "1_1") (pintype "passive"))
      (node (ref "R50") (pin "1") (pinfunction "1_1") (pintype "passive"))
      (node (ref "U2") (pin "15") (pinfunction "GND2_15") (pintype "power_in"))
      (node (ref "U2") (pin "9") (pinfunction "GND2_9") (pintype "power_in"))
      (node (ref "U4") (pin "27") (pinfunction "TSTPLL/48MCLK_27") (pintype "input"))
      (node (ref "U4") (pin "28") (pinfunction "GND_28") (pintype "power_in"))
      (node (ref "U4") (pin "31") (pinfunction "TSTMODE_31") (pintype "input"))
      (node (ref "U4") (pin "33") (pinfunction "EP_33") (pintype "passive"))
      (node (ref "U4") (pin "7") (pinfunction "GND_7") (pintype "power_in"))
      (node (ref "U5") (pin "14") (pinfunction "AVSS1_14") (pintype "power_in"))
      (node (ref "U5") (pin "16") (pinfunction "DVSS1_16") (pintype "power_in"))
      (node (ref "U5") (pin "39") (pinfunction "DVSS2_39") (pintype "power_in"))
      (node (ref "U5") (pin "49") (pinfunction "VSSU_49") (pintype "power_in"))
      (node (ref "U5") (pin "56") (pinfunction "AVSS2_56") (pintype "power_in"))
      (node (ref "U5") (pin "65") (pinfunction "QFN_PAD_65") (pintype "power_in"))
      (node (ref "Y2") (pin "2") (pinfunction "GND_2") (pintype "passive"))
      (node (ref "Y4") (pin "2") (pinfunction "GND_2") (pintype "passive"))
    )
    (net (code "37") (name "Net-(D1-K)") (class "Default")
      (node (ref "D1") (pin "2") (pinfunction "K_2") (pintype "passive"))
      (node (ref "R2") (pin "2") (pinfunction "2_2") (pintype "passive"))
    )
    (net (code "38") (name "Net-(D4-A)") (class "Default")
      (node (ref "D4") (pin "1") (pinfunction "A_1") (pintype "passive"))
      (node (ref "R40") (pin "1") (pinfunction "1_1") (pintype "passive"))
    )
    (net (code "39") (name "Net-(D6-A)") (class "Default")
      (node (ref "D6") (pin "1") (pinfunction "A_1") (pintype "passive"))
      (node (ref "R41") (pin "2") (pinfunction "2_2") (pintype "passive"))
    )
    (net (code "40") (name "Net-(U1-IO1)") (class "Default")
      (node (ref "C1") (pin "1") (pinfunction "1_1") (pintype "passive"))
      (node (ref "R1") (pin "2") (pinfunction "2_2") (pintype "passive"))
      (node (ref "U1") (pin "1") (pinfunction "IO1_1") (pintype "passive"))
      (node (ref "USB1") (pin "10") (pinfunction "10_10") (pintype "passive"))
      (node (ref "USB1") (pin "11") (pinfunction "11_11") (pintype "passive"))
      (node (ref "USB1") (pin "6") (pinfunction "6_6") (pintype "passive"))
      (node (ref "USB1") (pin "7") (pinfunction "7_7") (pintype "passive"))
      (node (ref "USB1") (pin "8") (pinfunction "8_8") (pintype "passive"))
      (node (ref "USB1") (pin "9") (pinfunction "9_9") (pintype "passive"))
    )
    (net (code "41") (name "Net-(U2-DD+)") (class "Default")
      (node (ref "R14") (pin "1") (pinfunction "1_1") (pintype "passive"))
      (node (ref "U2") (pin "10") (pinfunction "DD+_10") (pintype "bidirectional"))
    )
    (net (code "42") (name "Net-(U2-DD-)") (class "Default")
      (node (ref "R12") (pin "1") (pinfunction "1_1") (pintype "passive"))
      (node (ref "U2") (pin "11") (pinfunction "DD-_11") (pintype "bidirectional"))
    )
    (net (code "43") (name "Net-(U2-PDEN)") (class "Default")
      (node (ref "C4") (pin "2") (pinfunction "2_2") (pintype "passive"))
      (node (ref "U2") (pin "3") (pinfunction "VDD1_3") (pintype "power_in"))
      (node (ref "U2") (pin "4") (pinfunction "PDEN_4") (pintype "input"))
      (node (ref "U2") (pin "5") (pinfunction "SPU_5") (pintype "input"))
    )
    (net (code "44") (name "Net-(U2-UD+)") (class "Default")
      (node (ref "R4") (pin "2") (pinfunction "2_2") (pintype "passive"))
      (node (ref "U2") (pin "7") (pinfunction "UD+_7") (pintype "bidirectional"))
    )
    (net (code "45") (name "Net-(U2-UD-)") (class "Default")
      (node (ref "R3") (pin "2") (pinfunction "2_2") (pintype "passive"))
      (node (ref "U2") (pin "6") (pinfunction "UD-_6") (pintype "bidirectional"))
    )
    (net (code "46") (name "Net-(U4-DM1)") (class "Default")
      (node (ref "C19") (pin "1") (pinfunction "1_1") (pintype "passive"))
      (node (ref "R20") (pin "1") (pinfunction "1_1") (pintype "passive"))
      (node (ref "U4") (pin "11") (pinfunction "DM1_11") (pintype "bidirectional"))
    )
    (net (code "47") (name "Net-(U4-DM2)") (class "Default")
      (node (ref "C26") (pin "1") (pinfunction "1_1") (pintype "passive"))
      (node (ref "R24") (pin "1") (pinfunction "1_1") (pintype "passive"))
      (node (ref "U4") (pin "15") (pinfunction "DM2_15") (pintype "bidirectional"))
    )
    (net (code "48") (name "Net-(U4-DM3)") (class "Default")
      (node (ref "R31") (pin "1") (pinfunction "1_1") (pintype "passive"))
      (node (ref "U4") (pin "19") (pinfunction "DM3_19") (pintype "bidirectional"))
    )
    (net (code "49") (name "Net-(U4-DM4)") (class "Default")
      (node (ref "R29") (pin "1") (pinfunction "1_1") (pintype "passive"))
      (node (ref "U4") (pin "23") (pinfunction "DM4_23") (pintype "bidirectional"))
    )
    (net (code "50") (name "Net-(U4-DP1)") (class "Default")
      (node (ref "C23") (pin "1") (pinfunction "1_1") (pintype "passive"))
      (node (ref "R22") (pin "1") (pinfunction "1_1") (pintype "passive"))
      (node (ref "U4") (pin "12") (pinfunction "DP1_12") (pintype "bidirectional"))
    )
    (net (code "51") (name "Net-(U4-DP2)") (class "Default")
      (node (ref "C28") (pin "1") (pinfunction "1_1") (pintype "passive"))
      (node (ref "R25") (pin "1") (pinfunction "1_1") (pintype "passive"))
      (node (ref "U4") (pin "16") (pinfunction "DP2_16") (pintype "bidirectional"))
    )
    (net (code "52") (name "Net-(U4-DP3)") (class "Default")
      (node (ref "R30") (pin "1") (pinfunction "1_1") (pintype "passive"))
      (node (ref "U4") (pin "20") (pinfunction "DP3_20") (pintype "bidirectional"))
    )
    (net (code "53") (name "Net-(U4-DP4)") (class "Default")
      (node (ref "R26") (pin "1") (pinfunction "1_1") (pintype "passive"))
      (node (ref "U4") (pin "24") (pinfunction "DP4_24") (pintype "bidirectional"))
    )
    (net (code "54") (name "Net-(U4-XTAL1)") (class "Default")
      (node (ref "U4") (pin "30") (pinfunction "XTAL1_30") (pintype "passive"))
      (node (ref "Y2") (pin "1") (pinfunction "In_1") (pintype "passive"))
    )
    (net (code "55") (name "Net-(U4-XTAL2)") (class "Default")
      (node (ref "R23") (pin "1") (pinfunction "1_1") (pintype "passive"))
      (node (ref "U4") (pin "29") (pinfunction "XTAL2_29") (pintype "passive"))
    )
    (net (code "56") (name "Net-(U4-~{OVRCUR1})") (class "Default")
      (node (ref "R16") (pin "1") (pinfunction "1_1") (pintype "passive"))
      (node (ref "U4") (pin "10") (pinfunction "~{OVRCUR1}_10") (pintype "input"))
      (node (ref "U4") (pin "14") (pinfunction "~{OVRCUR2}_14") (pintype "input"))
      (node (ref "U4") (pin "18") (pinfunction "~{OVRCUR3}_18") (pintype "input"))
      (node (ref "U4") (pin "22") (pinfunction "~{OVRCUR4}_22") (pintype "input"))
    )
    (net (code "57") (name "Net-(U4-~{RESET})") (class "Default")
      (node (ref "C15") (pin "1") (pinfunction "1_1") (pintype "passive"))
      (node (ref "R17") (pin "1") (pinfunction "1_1") (pintype "passive"))
      (node (ref "U4") (pin "4") (pinfunction "~{RESET}_4") (pintype "input"))
    )
    (net (code "58") (name "Net-(U5-VCORE)") (class "Default")
      (node (ref "C35") (pin "2") (pinfunction "2_2") (pintype "passive"))
      (node (ref "U5") (pin "17") (pinfunction "VCORE_17") (pintype "passive"))
    )
    (net (code "59") (name "Net-(USB1-GND)") (class "Default")
      (node (ref "L1") (pin "1") (pinfunction "1_1") (pintype "passive"))
      (node (ref "USB1") (pin "5") (pinfunction "GND_5") (pintype "passive"))
    )
    (net (code "60") (name "Net-(USB1-VBUS)") (class "Default")
      (node (ref "L2") (pin "1") (pinfunction "1_1") (pintype "passive"))
      (node (ref "USB1") (pin "1") (pinfunction "VBUS_1") (pintype "passive"))
    )
    (net (code "61") (name "Net-(Y2-Out)") (class "Default")
      (node (ref "R23") (pin "2") (pinfunction "2_2") (pintype "passive"))
      (node (ref "Y2") (pin "3") (pinfunction "Out_3") (pintype "passive"))
    )
    (net (code "62") (name "USB_GND") (class "Default")
      (node (ref "C1") (pin "2") (pinfunction "2_2") (pintype "passive"))
      (node (ref "C2") (pin "2") (pinfunction "2_2") (pintype "passive"))
      (node (ref "C3") (pin "1") (pinfunction "1_1") (pintype "passive"))
      (node (ref "C4") (pin "1") (pinfunction "1_1") (pintype "passive"))
      (node (ref "L1") (pin "2") (pinfunction "2_2") (pintype "passive"))
      (node (ref "R1") (pin "1") (pinfunction "1_1") (pintype "passive"))
      (node (ref "R2") (pin "1") (pinfunction "1_1") (pintype "passive"))
      (node (ref "U1") (pin "3") (pinfunction "GND_3") (pintype "power_in"))
      (node (ref "U2") (pin "2") (pinfunction "GND1_2") (pintype "power_in"))
      (node (ref "U2") (pin "8") (pinfunction "GND1_8") (pintype "power_in"))
    )
    (net (code "63") (name "unconnected-(U1-IO2-Pad2)") (class "Default")
      (node (ref "U1") (pin "2") (pinfunction "IO2_2") (pintype "passive+no_connect"))
    )
    (net (code "64") (name "unconnected-(U4-EECLK-Pad5)") (class "Default")
      (node (ref "U4") (pin "5") (pinfunction "EECLK_5") (pintype "tri_state+no_connect"))
    )
    (net (code "65") (name "unconnected-(U4-SUSPND-Pad32)") (class "Default")
      (node (ref "U4") (pin "32") (pinfunction "SUSPND_32") (pintype "output+no_connect"))
    )
    (net (code "66") (name "unconnected-(U5-P1.0{slash}TA0CLK{slash}ACLK-Pad18)") (class "Default")
      (node (ref "U5") (pin "18") (pinfunction "P1.0/TA0CLK/ACLK_18") (pintype "bidirectional+no_connect"))
    )
    (net (code "67") (name "unconnected-(U5-P1.1{slash}TA0.0-Pad19)") (class "Default")
      (node (ref "U5") (pin "19") (pinfunction "P1.1/TA0.0_19") (pintype "bidirectional+no_connect"))
    )
    (net (code "68") (name "unconnected-(U5-P1.4{slash}TA0.3-Pad22)") (class "Default")
      (node (ref "U5") (pin "22") (pinfunction "P1.4/TA0.3_22") (pintype "bidirectional+no_connect"))
    )
    (net (code "69") (name "unconnected-(U5-P1.5{slash}TA0.4-Pad23)") (class "Default")
      (node (ref "U5") (pin "23") (pinfunction "P1.5/TA0.4_23") (pintype "bidirectional+no_connect"))
    )
    (net (code "70") (name "unconnected-(U5-P1.6{slash}TA1CLK{slash}CBOUT-Pad24)") (class "Default")
      (node (ref "U5") (pin "24") (pinfunction "P1.6/TA1CLK/CBOUT_24") (pintype "bidirectional+no_connect"))
    )
    (net (code "71") (name "unconnected-(U5-P1.7{slash}TA1.0-Pad25)") (class "Default")
      (node (ref "U5") (pin "25") (pinfunction "P1.7/TA1.0_25") (pintype "bidirectional+no_connect"))
    )
    (net (code "72") (name "unconnected-(U5-P2.0{slash}TA1.1-Pad26)") (class "Default")
      (node (ref "U5") (pin "26") (pinfunction "P2.0/TA1.1_26") (pintype "bidirectional+no_connect"))
    )
    (net (code "73") (name "unconnected-(U5-P2.1{slash}TA1.2-Pad27)") (class "Default")
      (node (ref "U5") (pin "27") (pinfunction "P2.1/TA1.2_27") (pintype "bidirectional+no_connect"))
    )
    (net (code "74") (name "unconnected-(U5-P2.2{slash}TA2CLK{slash}SMCLK-Pad28)") (class "Default")
      (node (ref "U5") (pin "28") (pinfunction "P2.2/TA2CLK/SMCLK_28") (pintype "bidirectional+no_connect"))
    )
    (net (code "75") (name "unconnected-(U5-P2.3{slash}TA2.0-Pad29)") (class "Default")
      (node (ref "U5") (pin "29") (pinfunction "P2.3/TA2.0_29") (pintype "bidirectional+no_connect"))
    )
    (net (code "76") (name "unconnected-(U5-P2.4{slash}TA2.1-Pad30)") (class "Default")
      (node (ref "U5") (pin "30") (pinfunction "P2.4/TA2.1_30") (pintype "bidirectional+no_connect"))
    )
    (net (code "77") (name "unconnected-(U5-P2.5{slash}TA2.2-Pad31)") (class "Default")
      (node (ref "U5") (pin "31") (pinfunction "P2.5/TA2.2_31") (pintype "bidirectional+no_connect"))
    )
    (net (code "78") (name "unconnected-(U5-P2.6{slash}RTCCLK{slash}DMAE0-Pad32)") (class "Default")
      (node (ref "U5") (pin "32") (pinfunction "P2.6/RTCCLK/DMAE0_32") (pintype "bidirectional+no_connect"))
    )
    (net (code "79") (name "unconnected-(U5-P2.7{slash}UCB0STE{slash}UCA0CLK-Pad33)") (class "Default")
      (node (ref "U5") (pin "33") (pinfunction "P2.7/UCB0STE/UCA0CLK_33") (pintype "bidirectional+no_connect"))
    )
    (net (code "80") (name "unconnected-(U5-P3.0{slash}UCB0SIMO{slash}UCB0SDA-Pad34)") (class "Default")
      (node (ref "U5") (pin "34") (pinfunction "P3.0/UCB0SIMO/UCB0SDA_34") (pintype "bidirectional+no_connect"))
    )
    (net (code "81") (name "unconnected-(U5-P3.1{slash}UCB0SOMI{slash}UCB0SCL-Pad35)") (class "Default")
      (node (ref "U5") (pin "35") (pinfunction "P3.1/UCB0SOMI/UCB0SCL_35") (pintype "bidirectional+no_connect"))
    )
    (net (code "82") (name "unconnected-(U5-P3.2{slash}UCB0CLK{slash}UCA0STE-Pad36)") (class "Default")
      (node (ref "U5") (pin "36") (pinfunction "P3.2/UCB0CLK/UCA0STE_36") (pintype "bidirectional+no_connect"))
    )
    (net (code "83") (name "unconnected-(U5-P4.0{slash}PM_UCB1STE{slash}PM_UCA1CLK-Pad41)") (class "Default")
      (node (ref "U5") (pin "41") (pinfunction "P4.0/PM_UCB1STE/PM_UCA1CLK_41") (pintype "bidirectional+no_connect"))
    )
    (net (code "84") (name "unconnected-(U5-P4.1{slash}PM_UCB1SIMO{slash}PM_UCB1SDA-Pad42)") (class "Default")
      (node (ref "U5") (pin "42") (pinfunction "P4.1/PM_UCB1SIMO/PM_UCB1SDA_42") (pintype "bidirectional+no_connect"))
    )
    (net (code "85") (name "unconnected-(U5-P4.5{slash}PM_UCA1RXD{slash}PM_UCA1SOMI-Pad46)") (class "Default")
      (node (ref "U5") (pin "46") (pinfunction "P4.5/PM_UCA1RXD/PM_UCA1SOMI_46") (pintype "bidirectional+no_connect"))
    )
    (net (code "86") (name "unconnected-(U5-P4.6{slash}PM_NONE-Pad47)") (class "Default")
      (node (ref "U5") (pin "47") (pinfunction "P4.6/PM_NONE_47") (pintype "bidirectional+no_connect"))
    )
    (net (code "87") (name "unconnected-(U5-P4.7{slash}PM_NONE-Pad48)") (class "Default")
      (node (ref "U5") (pin "48") (pinfunction "P4.7/PM_NONE_48") (pintype "bidirectional+no_connect"))
    )
    (net (code "88") (name "unconnected-(U5-P5.1{slash}A9{slash}VREF-{slash}VEREF--Pad10)") (class "Default")
      (node (ref "U5") (pin "10") (pinfunction "P5.1/A9/VREF-/VEREF-_10") (pintype "bidirectional+no_connect"))
    )
    (net (code "89") (name "unconnected-(U5-P5.4{slash}XIN-Pad12)") (class "Default")
      (node (ref "U5") (pin "12") (pinfunction "P5.4/XIN_12") (pintype "bidirectional+no_connect"))
    )
    (net (code "90") (name "unconnected-(U5-P5.5{slash}XOUT-Pad13)") (class "Default")
      (node (ref "U5") (pin "13") (pinfunction "P5.5/XOUT_13") (pintype "bidirectional+no_connect"))
    )
    (net (code "91") (name "unconnected-(U5-P6.2{slash}CB2{slash}A2-Pad3)") (class "Default")
      (node (ref "U5") (pin "3") (pinfunction "P6.2/CB2/A2_3") (pintype "bidirectional+no_connect"))
    )
    (net (code "92") (name "unconnected-(U5-P6.3{slash}CB3{slash}A3-Pad4)") (class "Default")
      (node (ref "U5") (pin "4") (pinfunction "P6.3/CB3/A3_4") (pintype "bidirectional+no_connect"))
    )
    (net (code "93") (name "unconnected-(U5-P6.4{slash}CB4{slash}A4-Pad5)") (class "Default")
      (node (ref "U5") (pin "5") (pinfunction "P6.4/CB4/A4_5") (pintype "bidirectional+no_connect"))
    )
    (net (code "94") (name "unconnected-(U5-P6.5{slash}CB5{slash}A5-Pad6)") (class "Default")
      (node (ref "U5") (pin "6") (pinfunction "P6.5/CB5/A5_6") (pintype "bidirectional+no_connect"))
    )
    (net (code "95") (name "unconnected-(U5-P6.6{slash}CB6{slash}A6-Pad7)") (class "Default")
      (node (ref "U5") (pin "7") (pinfunction "P6.6/CB6/A6_7") (pintype "bidirectional+no_connect"))
    )
    (net (code "96") (name "unconnected-(U5-P6.7{slash}CB7{slash}A7-Pad8)") (class "Default")
      (node (ref "U5") (pin "8") (pinfunction "P6.7/CB7/A7_8") (pintype "bidirectional+no_connect"))
    )
    (net (code "97") (name "unconnected-(USB1-ID-Pad4)") (class "Default")
      (node (ref "USB1") (pin "4") (pinfunction "ID_4") (pintype "passive"))
    )
  )
)
